# EE3102_PCB_Proj.net
KiCad netlist of a schematic drawn in Altium Designer
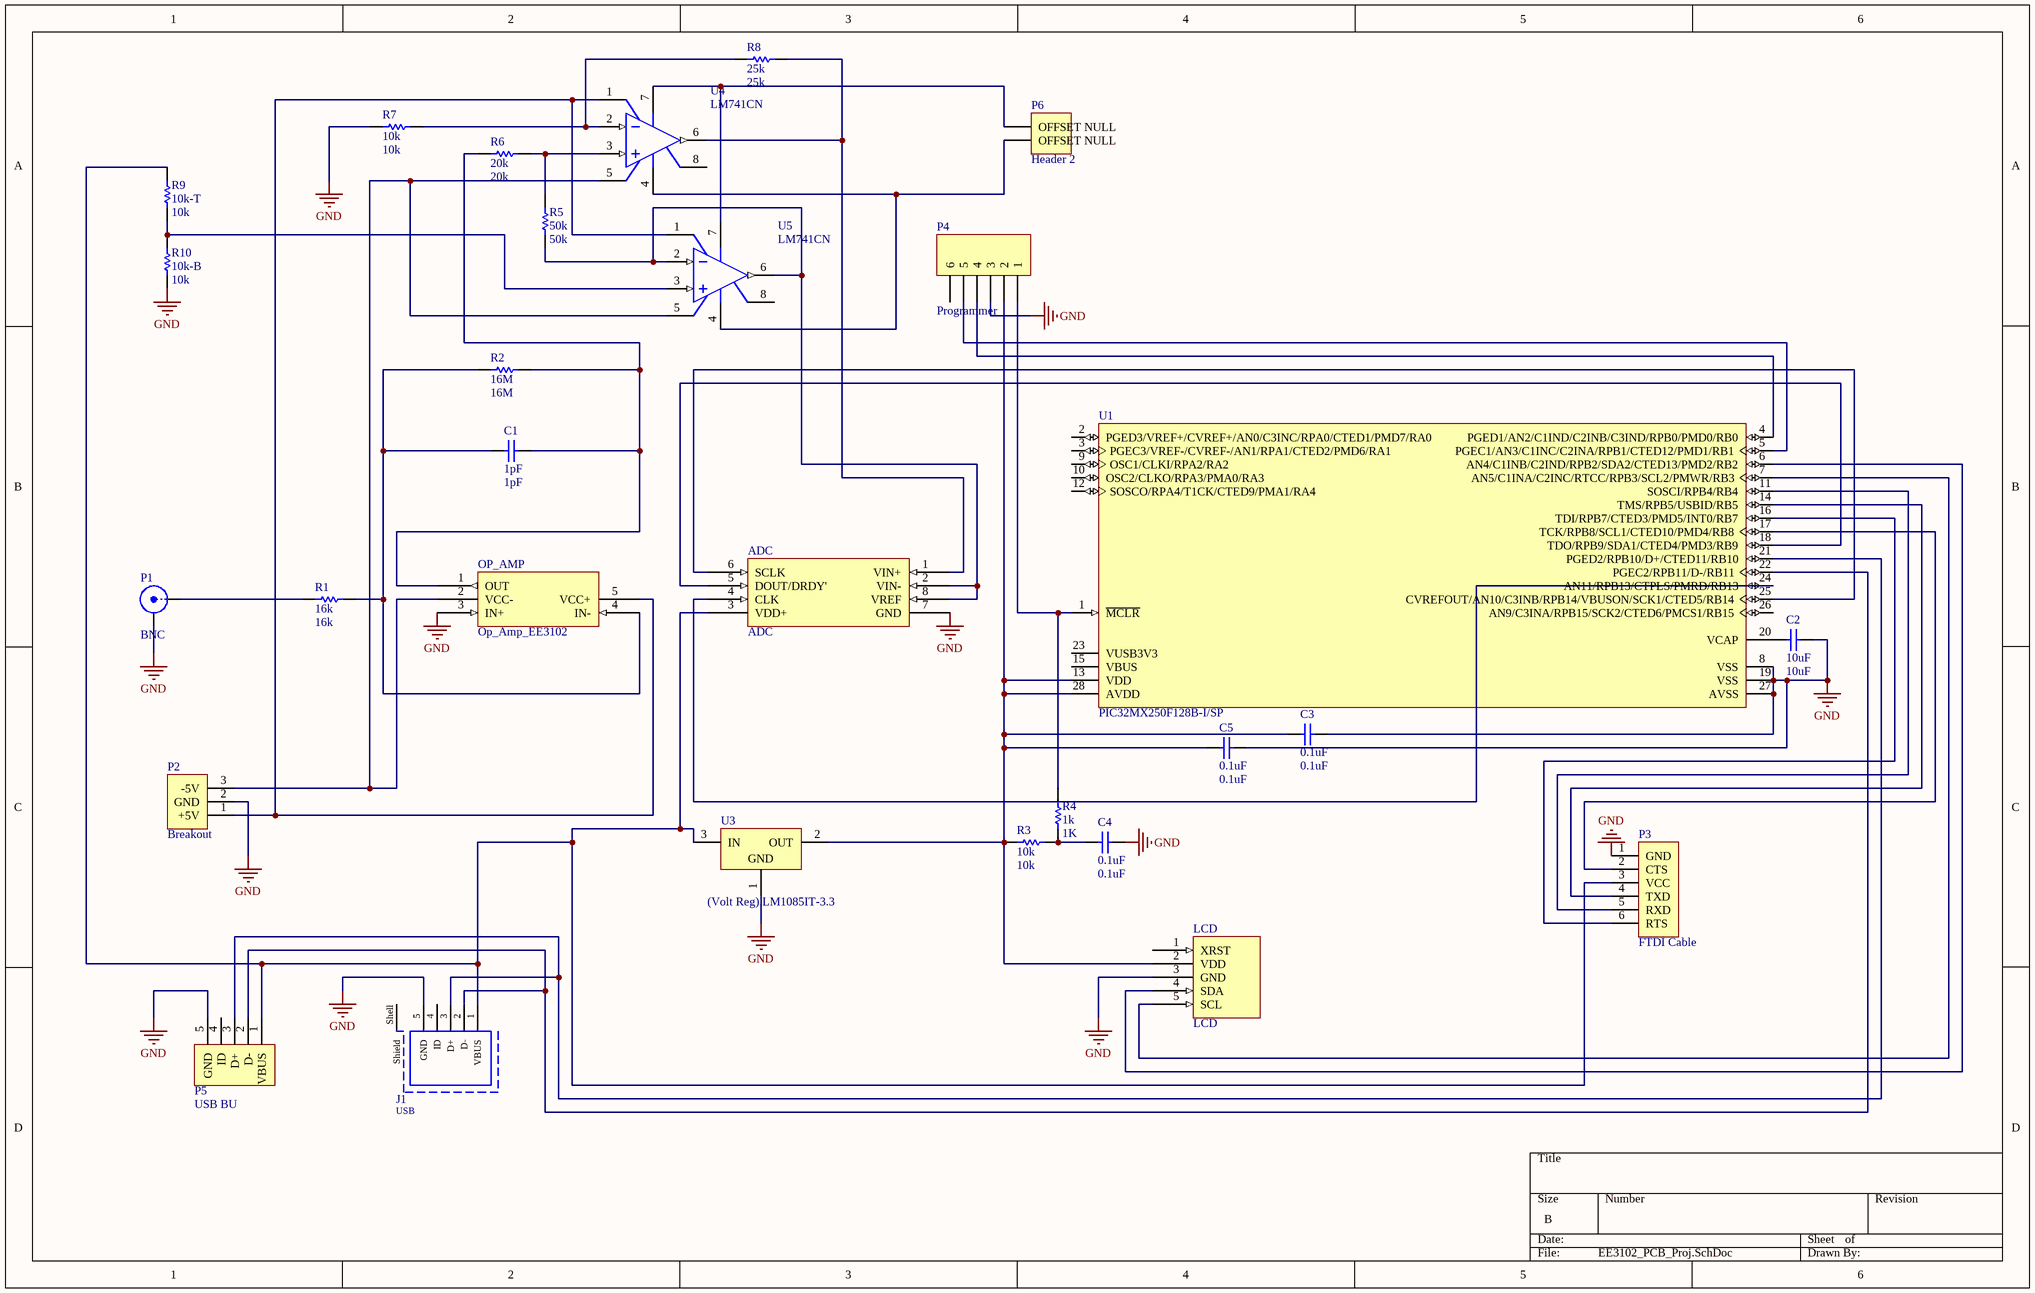
[diagram p0: EE3102_PCB_Proj.SchDoc]

(export (version "E")
  (design (tool "Eeschema 10.0.6"))
  (components
    (comp (ref "ADC") (value "ADC") (footprint "ADC") (libsource (lib "EE3102_PCB_Proj_Lib") (part "ADC")))
    (comp (ref "C1")
      (value "1pF")
      (footprint "RAD-0.3")
      (description "Capacitor")
      (fields (field (name "ALTIUM_VALUE") "1pF") (field (name "PUBLISHER") "Altium Limited"))
      (libsource (lib "Miscellaneous Devices") (part "Cap"))
    )
    (comp (ref "C2")
      (value "10uF")
      (footprint "RAD-0.3")
      (description "Capacitor")
      (fields (field (name "ALTIUM_VALUE") "10uF") (field (name "PUBLISHER") "Altium Limited"))
      (libsource (lib "Miscellaneous Devices") (part "Cap"))
    )
    (comp (ref "C3")
      (value "0.1uF")
      (footprint "RAD-0.3")
      (description "Capacitor")
      (fields (field (name "ALTIUM_VALUE") "0.1uF") (field (name "PUBLISHER") "Altium Limited"))
      (libsource (lib "Miscellaneous Devices") (part "Cap"))
    )
    (comp (ref "C4")
      (value "0.1uF")
      (footprint "RAD-0.3")
      (description "Capacitor")
      (fields (field (name "ALTIUM_VALUE") "0.1uF") (field (name "PUBLISHER") "Altium Limited"))
      (libsource (lib "Miscellaneous Devices") (part "Cap"))
    )
    (comp (ref "C5")
      (value "0.1uF")
      (footprint "RAD-0.3")
      (description "Capacitor")
      (fields (field (name "ALTIUM_VALUE") "0.1uF") (field (name "PUBLISHER") "Altium Limited"))
      (libsource (lib "Miscellaneous Devices") (part "Cap"))
    )
    (comp (ref "J1")
      (value "USB")
      (footprint "629105150921")
      (description "Micro USB 2.0 Type AB Receptacle WR-COM, Horizontal, SMT")
      (fields (field (name "PART NUMBER") "629105150921") (field (name "PUBLISHER") "Wurth Elektronik"))
      (libsource (lib "ALTIUM-WR-COM_USB_20-rev18d") (part "629105150921"))
    )
    (comp (ref "LCD") (value "LCD") (footprint "LCD") (libsource (lib "EE3102_PCB_Proj_Lib") (part "LCD")))
    (comp (ref "OP_AMP")
      (value "Op_Amp_EE3102")
      (footprint "Op_Amp")
      (libsource (lib "EE3102_PCB_Proj_Lib") (part "Op_Amp"))
    )
    (comp (ref "P1")
      (value "BNC")
      (footprint "BNC_RA CON")
      (description "BNC Elbow Connector")
      (fields (field (name "PUBLISHER") "Altium Limited"))
      (libsource (lib "Miscellaneous Connectors") (part "BNC"))
    )
    (comp (ref "P2")
      (value "Breakout")
      (footprint "HDR1X3")
      (description "Header, 3-Pin")
      (fields (field (name "PUBLISHER") "Altium Limited"))
      (libsource (lib "Miscellaneous Connectors") (part "Header 3"))
    )
    (comp (ref "P3")
      (value "FTDI Cable")
      (footprint "HDR1X6")
      (description "Header, 6-Pin")
      (fields (field (name "PUBLISHER") "Altium Limited"))
      (libsource (lib "") (part "Header 6_1"))
    )
    (comp (ref "P4")
      (value "Programmer")
      (footprint "HDR1X6")
      (description "Header, 6-Pin")
      (fields (field (name "PUBLISHER") "Altium Limited"))
      (libsource (lib "Miscellaneous Connectors") (part "Header 6"))
    )
    (comp (ref "P5")
      (value "USB BU")
      (footprint "HDR1X5")
      (description "Header, 5-Pin")
      (fields (field (name "PUBLISHER") "Altium Limited"))
      (libsource (lib "Miscellaneous Connectors") (part "Header 5"))
    )
    (comp (ref "P6")
      (value "Header 2")
      (footprint "HDR1X2")
      (description "Header, 2-Pin")
      (fields (field (name "PUBLISHER") "Altium Limited"))
      (libsource (lib "Miscellaneous Connectors") (part "Header 2"))
    )
    (comp (ref "R1")
      (value "16k")
      (footprint "AXIAL-0.3")
      (description "Resistor")
      (fields (field (name "ALTIUM_VALUE") "16k") (field (name "PUBLISHER") "Altium Limited"))
      (libsource (lib "Miscellaneous Devices") (part "Res1"))
    )
    (comp (ref "R2")
      (value "16M")
      (footprint "AXIAL-0.3")
      (description "Resistor")
      (fields (field (name "ALTIUM_VALUE") "16M") (field (name "PUBLISHER") "Altium Limited"))
      (libsource (lib "Miscellaneous Devices") (part "Res1"))
    )
    (comp (ref "R3")
      (value "10k")
      (footprint "AXIAL-0.3")
      (description "Resistor")
      (fields (field (name "ALTIUM_VALUE") "10k") (field (name "PUBLISHER") "Altium Limited"))
      (libsource (lib "Miscellaneous Devices") (part "Res1"))
    )
    (comp (ref "R4")
      (value "1k")
      (footprint "AXIAL-0.3")
      (description "Resistor")
      (fields (field (name "ALTIUM_VALUE") "1K") (field (name "PUBLISHER") "Altium Limited"))
      (libsource (lib "Miscellaneous Devices") (part "Res1"))
    )
    (comp (ref "R5")
      (value "50k")
      (footprint "AXIAL-0.3")
      (description "Resistor")
      (fields (field (name "ALTIUM_VALUE") "50k") (field (name "PUBLISHER") "Altium Limited"))
      (libsource (lib "Miscellaneous Devices") (part "Res1"))
    )
    (comp (ref "R6")
      (value "20k")
      (footprint "AXIAL-0.3")
      (description "Resistor")
      (fields (field (name "ALTIUM_VALUE") "20k") (field (name "PUBLISHER") "Altium Limited"))
      (libsource (lib "Miscellaneous Devices") (part "Res1"))
    )
    (comp (ref "R7")
      (value "10k")
      (footprint "AXIAL-0.3")
      (description "Resistor")
      (fields (field (name "ALTIUM_VALUE") "10k") (field (name "PUBLISHER") "Altium Limited"))
      (libsource (lib "Miscellaneous Devices") (part "Res1"))
    )
    (comp (ref "R8")
      (value "25k")
      (footprint "AXIAL-0.3")
      (description "Resistor")
      (fields (field (name "ALTIUM_VALUE") "25k") (field (name "PUBLISHER") "Altium Limited"))
      (libsource (lib "Miscellaneous Devices") (part "Res1"))
    )
    (comp (ref "R9")
      (value "10k-T")
      (footprint "AXIAL-0.3")
      (description "Resistor")
      (fields (field (name "ALTIUM_VALUE") "10k") (field (name "PUBLISHER") "Altium Limited"))
      (libsource (lib "Miscellaneous Devices") (part "Res1"))
    )
    (comp (ref "R10")
      (value "10k-B")
      (footprint "AXIAL-0.3")
      (description "Resistor")
      (fields (field (name "ALTIUM_VALUE") "10k") (field (name "PUBLISHER") "Altium Limited"))
      (libsource (lib "Miscellaneous Devices") (part "Res1"))
    )
    (comp (ref "U1")
      (value "PIC32MX250F128B-I/SP")
      (footprint "MCHP-SPDIP-SP28")
      (fields (field (name "MANUFACTURER") "Microchip"))
      (libsource (lib "Microchip PIC32MX") (part "PIC32MX250F128B-I/SP"))
    )
    (comp (ref "U3")
      (value "(Volt Reg) LM1085IT-3.3")
      (footprint "T03B")
      (description "3A Low Dropout Positive Regulators, 3-pin TO-220")
      (fields
        (field (name "PARTNUMBER") "LM1085IT-3.3")
        (field (name "MANUFACTURER") "National Semiconductor")
      )
      (libsource (lib "National Semiconductor LDO") (part "LM1085IT-3.3"))
    )
    (comp (ref "U4")
      (value "LM741CN")
      (footprint "N08E")
      (description "Operational Amplifier, 8-pin MDIP")
      (fields (field (name "MANUFACTURER") "National Semiconductor"))
      (libsource (lib "National Semiconductor Amplifier") (part "LM741CN"))
    )
    (comp (ref "U5")
      (value "LM741CN")
      (footprint "N08E")
      (description "Operational Amplifier, 8-pin MDIP")
      (fields (field (name "MANUFACTURER") "National Semiconductor"))
      (libsource (lib "National Semiconductor Amplifier") (part "LM741CN"))
    )
  )
  (nets
    (net (code "1") (name "GND") (class "Default")
      (node (ref "ADC") (pin "7") (pinfunction "GND_7") (pintype "power_in"))
      (node (ref "C2") (pin "2") (pinfunction "2_2") (pintype "passive"))
      (node (ref "C3") (pin "2") (pinfunction "2_2") (pintype "passive"))
      (node (ref "C4") (pin "2") (pinfunction "2_2") (pintype "passive"))
      (node (ref "C5") (pin "2") (pinfunction "2_2") (pintype "passive"))
      (node (ref "J1") (pin "5") (pinfunction "GND_5") (pintype "passive"))
      (node (ref "LCD") (pin "3") (pinfunction "GND_3") (pintype "power_in"))
      (node (ref "OP_AMP") (pin "3") (pinfunction "IN+_3") (pintype "input"))
      (node (ref "P1") (pin "2") (pinfunction "Y_2") (pintype "passive"))
      (node (ref "P2") (pin "2") (pinfunction "GND_2") (pintype "passive"))
      (node (ref "P3") (pin "1") (pinfunction "GND_1") (pintype "passive"))
      (node (ref "P4") (pin "3") (pinfunction "3_3") (pintype "passive"))
      (node (ref "P5") (pin "5") (pinfunction "GND_5") (pintype "passive"))
      (node (ref "R10") (pin "1") (pinfunction "1_1") (pintype "passive"))
      (node (ref "R7") (pin "1") (pinfunction "1_1") (pintype "passive"))
      (node (ref "U1") (pin "19") (pinfunction "VSS_19") (pintype "power_in"))
      (node (ref "U1") (pin "27") (pinfunction "AVSS_27") (pintype "power_in"))
      (node (ref "U1") (pin "8") (pinfunction "VSS_8") (pintype "power_in"))
      (node (ref "U3") (pin "1") (pinfunction "GND_1") (pintype "power_in"))
    )
    (net (code "2") (name "Net-(ADC-CLK)") (class "Default")
      (node (ref "ADC") (pin "4") (pinfunction "CLK_4") (pintype "input"))
      (node (ref "U1") (pin "24") (pinfunction "AN11/RPB13/CTPLS/PMRD/RB13_24") (pintype "bidirectional"))
    )
    (net (code "3") (name "Net-(ADC-DOUT{slash}DRDY')") (class "Default")
      (node (ref "ADC") (pin "5") (pinfunction "DOUT/DRDY'_5") (pintype "input"))
      (node (ref "U1") (pin "18") (pinfunction "TDO/RPB9/SDA1/CTED4/PMD3/RB9_18") (pintype "bidirectional"))
    )
    (net (code "4") (name "Net-(ADC-SCLK)") (class "Default")
      (node (ref "ADC") (pin "6") (pinfunction "SCLK_6") (pintype "input"))
      (node (ref "U1") (pin "25") (pinfunction "CVREFOUT/AN10/C3INB/RPB14/VBUSON/SCK1/CTED5/RB14_25") (pintype "bidirectional"))
    )
    (net (code "5") (name "Net-(ADC-VDD+)") (class "Default")
      (node (ref "ADC") (pin "3") (pinfunction "VDD+_3") (pintype "power_in"))
      (node (ref "J1") (pin "1") (pinfunction "VBUS_1") (pintype "passive"))
      (node (ref "P3") (pin "3") (pinfunction "VCC_3") (pintype "passive"))
      (node (ref "P5") (pin "1") (pinfunction "VBUS_1") (pintype "passive"))
      (node (ref "R9") (pin "2") (pinfunction "2_2") (pintype "passive"))
      (node (ref "U3") (pin "3") (pinfunction "IN_3") (pintype "power_in"))
    )
    (net (code "6") (name "Net-(ADC-VIN+)") (class "Default")
      (node (ref "ADC") (pin "1") (pinfunction "VIN+_1") (pintype "input"))
      (node (ref "R8") (pin "2") (pinfunction "2_2") (pintype "passive"))
      (node (ref "U4") (pin "6") (pinfunction "OUT_6") (pintype "output"))
    )
    (net (code "7") (name "Net-(ADC-VIN-)") (class "Default")
      (node (ref "ADC") (pin "2") (pinfunction "VIN-_2") (pintype "input"))
      (node (ref "ADC") (pin "8") (pinfunction "VREF_8") (pintype "input"))
      (node (ref "R5") (pin "2") (pinfunction "2_2") (pintype "passive"))
      (node (ref "U5") (pin "2") (pinfunction "IN-_2") (pintype "input"))
      (node (ref "U5") (pin "6") (pinfunction "OUT_6") (pintype "output"))
    )
    (net (code "8") (name "Net-(C4-Pad1)") (class "Default")
      (node (ref "C4") (pin "1") (pinfunction "1_1") (pintype "passive"))
      (node (ref "R3") (pin "1") (pinfunction "1_1") (pintype "passive"))
      (node (ref "R4") (pin "1") (pinfunction "1_1") (pintype "passive"))
    )
    (net (code "9") (name "Net-(J1-D+)") (class "Default")
      (node (ref "J1") (pin "3") (pinfunction "D+_3") (pintype "passive"))
      (node (ref "P5") (pin "3") (pinfunction "D+_3") (pintype "passive"))
      (node (ref "U1") (pin "21") (pinfunction "PGED2/RPB10/D+/CTED11/RB10_21") (pintype "bidirectional"))
    )
    (net (code "10") (name "Net-(J1-D-)") (class "Default")
      (node (ref "J1") (pin "2") (pinfunction "D-_2") (pintype "passive"))
      (node (ref "P5") (pin "2") (pinfunction "D-_2") (pintype "passive"))
      (node (ref "U1") (pin "22") (pinfunction "PGEC2/RPB11/D-/RB11_22") (pintype "bidirectional"))
    )
    (net (code "11") (name "Net-(LCD-SCL)") (class "Default")
      (node (ref "LCD") (pin "5") (pinfunction "SCL_5") (pintype "input"))
      (node (ref "U1") (pin "7") (pinfunction "AN5/C1INA/C2INC/RTCC/RPB3/SCL2/PMWR/RB3_7") (pintype "bidirectional"))
    )
    (net (code "12") (name "Net-(LCD-SDA)") (class "Default")
      (node (ref "LCD") (pin "4") (pinfunction "SDA_4") (pintype "input"))
      (node (ref "U1") (pin "6") (pinfunction "AN4/C1INB/C2IND/RPB2/SDA2/CTED13/PMD2/RB2_6") (pintype "bidirectional"))
    )
    (net (code "13") (name "Net-(LCD-VDD)") (class "Default")
      (node (ref "C3") (pin "1") (pinfunction "1_1") (pintype "passive"))
      (node (ref "C5") (pin "1") (pinfunction "1_1") (pintype "passive"))
      (node (ref "LCD") (pin "2") (pinfunction "VDD_2") (pintype "power_in"))
      (node (ref "P4") (pin "2") (pinfunction "2_2") (pintype "passive"))
      (node (ref "R3") (pin "2") (pinfunction "2_2") (pintype "passive"))
      (node (ref "U1") (pin "13") (pinfunction "VDD_13") (pintype "power_in"))
      (node (ref "U1") (pin "28") (pinfunction "AVDD_28") (pintype "power_in"))
      (node (ref "U3") (pin "2") (pinfunction "OUT_2") (pintype "power_in"))
    )
    (net (code "14") (name "Net-(OP_AMP-IN-)") (class "Default")
      (node (ref "C1") (pin "1") (pinfunction "1_1") (pintype "passive"))
      (node (ref "OP_AMP") (pin "4") (pinfunction "IN-_4") (pintype "input"))
      (node (ref "R1") (pin "2") (pinfunction "2_2") (pintype "passive"))
      (node (ref "R2") (pin "1") (pinfunction "1_1") (pintype "passive"))
    )
    (net (code "15") (name "Net-(OP_AMP-OUT)") (class "Default")
      (node (ref "C1") (pin "2") (pinfunction "2_2") (pintype "passive"))
      (node (ref "OP_AMP") (pin "1") (pinfunction "OUT_1") (pintype "output"))
      (node (ref "R2") (pin "2") (pinfunction "2_2") (pintype "passive"))
      (node (ref "R6") (pin "1") (pinfunction "1_1") (pintype "passive"))
    )
    (net (code "16") (name "Net-(OP_AMP-VCC+)") (class "Default")
      (node (ref "OP_AMP") (pin "5") (pinfunction "VCC+_5") (pintype "power_in"))
      (node (ref "P2") (pin "1") (pinfunction "+5V_1") (pintype "passive"))
      (node (ref "U4") (pin "1") (pinfunction "OFS_NULL_1") (pintype "passive"))
      (node (ref "U5") (pin "1") (pinfunction "OFS_NULL_1") (pintype "passive"))
    )
    (net (code "17") (name "Net-(OP_AMP-VCC-)") (class "Default")
      (node (ref "OP_AMP") (pin "2") (pinfunction "VCC-_2") (pintype "power_in"))
      (node (ref "P2") (pin "3") (pinfunction "-5V_3") (pintype "passive"))
      (node (ref "U4") (pin "5") (pinfunction "OFS_NULL_5") (pintype "passive"))
      (node (ref "U5") (pin "5") (pinfunction "OFS_NULL_5") (pintype "passive"))
    )
    (net (code "18") (name "Net-(P1-X)") (class "Default")
      (node (ref "P1") (pin "1") (pinfunction "X_1") (pintype "passive"))
      (node (ref "R1") (pin "1") (pinfunction "1_1") (pintype "passive"))
    )
    (net (code "19") (name "Net-(P3-CTS)") (class "Default")
      (node (ref "P3") (pin "2") (pinfunction "CTS_2") (pintype "passive"))
      (node (ref "U1") (pin "17") (pinfunction "TCK/RPB8/SCL1/CTED10/PMD4/RB8_17") (pintype "bidirectional"))
    )
    (net (code "20") (name "Net-(P3-RTS)") (class "Default")
      (node (ref "P3") (pin "6") (pinfunction "RTS_6") (pintype "passive"))
      (node (ref "U1") (pin "16") (pinfunction "TDI/RPB7/CTED3/PMD5/INT0/RB7_16") (pintype "bidirectional"))
    )
    (net (code "21") (name "Net-(P3-RXD)") (class "Default")
      (node (ref "P3") (pin "5") (pinfunction "RXD_5") (pintype "passive"))
      (node (ref "U1") (pin "11") (pinfunction "SOSCI/RPB4/RB4_11") (pintype "bidirectional"))
    )
    (net (code "22") (name "Net-(P3-TXD)") (class "Default")
      (node (ref "P3") (pin "4") (pinfunction "TXD_4") (pintype "passive"))
      (node (ref "U1") (pin "14") (pinfunction "TMS/RPB5/USBID/RB5_14") (pintype "bidirectional"))
    )
    (net (code "23") (name "Net-(U1-PGEC1{slash}AN3{slash}C1INC{slash}C2INA{slash}RPB1{slash}CTED12{slash}PMD1{slash}RB1)") (class "Default")
      (node (ref "P4") (pin "5") (pinfunction "5_5") (pintype "passive"))
      (node (ref "U1") (pin "5") (pinfunction "PGEC1/AN3/C1INC/C2INA/RPB1/CTED12/PMD1/RB1_5") (pintype "bidirectional"))
    )
    (net (code "24") (name "Net-(U1-PGED1{slash}AN2{slash}C1IND{slash}C2INB{slash}C3IND{slash}RPB0{slash}PMD0{slash}RB0)") (class "Default")
      (node (ref "P4") (pin "4") (pinfunction "4_4") (pintype "passive"))
      (node (ref "U1") (pin "4") (pinfunction "PGED1/AN2/C1IND/C2INB/C3IND/RPB0/PMD0/RB0_4") (pintype "bidirectional"))
    )
    (net (code "25") (name "Net-(U1-VCAP)") (class "Default")
      (node (ref "C2") (pin "1") (pinfunction "1_1") (pintype "passive"))
      (node (ref "U1") (pin "20") (pinfunction "VCAP_20") (pintype "passive"))
    )
    (net (code "26") (name "Net-(U1-~{MCLR})") (class "Default")
      (node (ref "P4") (pin "1") (pinfunction "1_1") (pintype "passive"))
      (node (ref "R4") (pin "2") (pinfunction "2_2") (pintype "passive"))
      (node (ref "U1") (pin "1") (pinfunction "~{MCLR}_1") (pintype "input"))
    )
    (net (code "27") (name "Net-(U4-IN+)") (class "Default")
      (node (ref "R5") (pin "1") (pinfunction "1_1") (pintype "passive"))
      (node (ref "R6") (pin "2") (pinfunction "2_2") (pintype "passive"))
      (node (ref "U4") (pin "3") (pinfunction "IN+_3") (pintype "input"))
    )
    (net (code "28") (name "Net-(U4-IN-)") (class "Default")
      (node (ref "R7") (pin "2") (pinfunction "2_2") (pintype "passive"))
      (node (ref "R8") (pin "1") (pinfunction "1_1") (pintype "passive"))
      (node (ref "U4") (pin "2") (pinfunction "IN-_2") (pintype "input"))
    )
    (net (code "29") (name "Net-(U4-V+)") (class "Default")
      (node (ref "P6") (pin "1") (pinfunction "OFFSET_NULL_1") (pintype "passive"))
      (node (ref "U4") (pin "7") (pinfunction "V+_7") (pintype "power_in"))
      (node (ref "U5") (pin "7") (pinfunction "V+_7") (pintype "power_in"))
    )
    (net (code "30") (name "Net-(U4-V-)") (class "Default")
      (node (ref "P6") (pin "2") (pinfunction "OFFSET_NULL_2") (pintype "passive"))
      (node (ref "U4") (pin "4") (pinfunction "V-_4") (pintype "power_in"))
      (node (ref "U5") (pin "4") (pinfunction "V-_4") (pintype "power_in"))
    )
    (net (code "31") (name "Net-(U5-IN+)") (class "Default")
      (node (ref "R10") (pin "2") (pinfunction "2_2") (pintype "passive"))
      (node (ref "R9") (pin "1") (pinfunction "1_1") (pintype "passive"))
      (node (ref "U5") (pin "3") (pinfunction "IN+_3") (pintype "input"))
    )
    (net (code "32") (name "unconnected-(J1-ID-Pad4)") (class "Default")
      (node (ref "J1") (pin "4") (pinfunction "ID_4") (pintype "passive"))
    )
    (net (code "33") (name "unconnected-(J1-Shield-PadShell)") (class "Default")
      (node (ref "J1") (pin "Shell") (pinfunction "Shield_Shell") (pintype "passive"))
    )
    (net (code "34") (name "unconnected-(LCD-XRST-Pad1)") (class "Default")
      (node (ref "LCD") (pin "1") (pinfunction "XRST_1") (pintype "input"))
    )
    (net (code "35") (name "unconnected-(P4-Pad6)") (class "Default")
      (node (ref "P4") (pin "6") (pinfunction "6_6") (pintype "passive"))
    )
    (net (code "36") (name "unconnected-(P5-ID-Pad4)") (class "Default")
      (node (ref "P5") (pin "4") (pinfunction "ID_4") (pintype "passive"))
    )
    (net (code "37") (name "unconnected-(U1-AN9{slash}C3INA{slash}RPB15{slash}SCK2{slash}CTED6{slash}PMCS1{slash}RB15-Pad26)") (class "Default")
      (node (ref "U1") (pin "26") (pinfunction "AN9/C3INA/RPB15/SCK2/CTED6/PMCS1/RB15_26") (pintype "bidirectional"))
    )
    (net (code "38") (name "unconnected-(U1-OSC1{slash}CLKI{slash}RPA2{slash}RA2-Pad9)") (class "Default")
      (node (ref "U1") (pin "9") (pinfunction "OSC1/CLKI/RPA2/RA2_9") (pintype "bidirectional"))
    )
    (net (code "39") (name "unconnected-(U1-OSC2{slash}CLKO{slash}RPA3{slash}PMA0{slash}RA3-Pad10)") (class "Default")
      (node (ref "U1") (pin "10") (pinfunction "OSC2/CLKO/RPA3/PMA0/RA3_10") (pintype "bidirectional"))
    )
    (net (code "40") (name "unconnected-(U1-PGEC3{slash}VREF-{slash}CVREF-{slash}AN1{slash}RPA1{slash}CTED2{slash}PMD6{slash}RA1-Pad3)") (class "Default")
      (node (ref "U1") (pin "3") (pinfunction "PGEC3/VREF-/CVREF-/AN1/RPA1/CTED2/PMD6/RA1_3") (pintype "bidirectional"))
    )
    (net (code "41") (name "unconnected-(U1-PGED3{slash}VREF+{slash}CVREF+{slash}AN0{slash}C3INC{slash}RPA0{slash}CTED1{slash}PMD7{slash}RA0-Pad2)") (class "Default")
      (node (ref "U1") (pin "2") (pinfunction "PGED3/VREF+/CVREF+/AN0/C3INC/RPA0/CTED1/PMD7/RA0_2") (pintype "bidirectional"))
    )
    (net (code "42") (name "unconnected-(U1-SOSCO{slash}RPA4{slash}T1CK{slash}CTED9{slash}PMA1{slash}RA4-Pad12)") (class "Default")
      (node (ref "U1") (pin "12") (pinfunction "SOSCO/RPA4/T1CK/CTED9/PMA1/RA4_12") (pintype "bidirectional"))
    )
    (net (code "43") (name "unconnected-(U1-VBUS-Pad15)") (class "Default")
      (node (ref "U1") (pin "15") (pinfunction "VBUS_15") (pintype "power_in"))
    )
    (net (code "44") (name "unconnected-(U1-VUSB3V3-Pad23)") (class "Default")
      (node (ref "U1") (pin "23") (pinfunction "VUSB3V3_23") (pintype "power_in"))
    )
    (net (code "45") (name "unconnected-(U4-NC-Pad8)") (class "Default")
      (node (ref "U4") (pin "8") (pinfunction "NC_8") (pintype "passive"))
    )
    (net (code "46") (name "unconnected-(U5-NC-Pad8)") (class "Default")
      (node (ref "U5") (pin "8") (pinfunction "NC_8") (pintype "passive"))
    )
  )
)
